# robot_driver_board.net
KiCad netlist of a schematic drawn in EAGLE
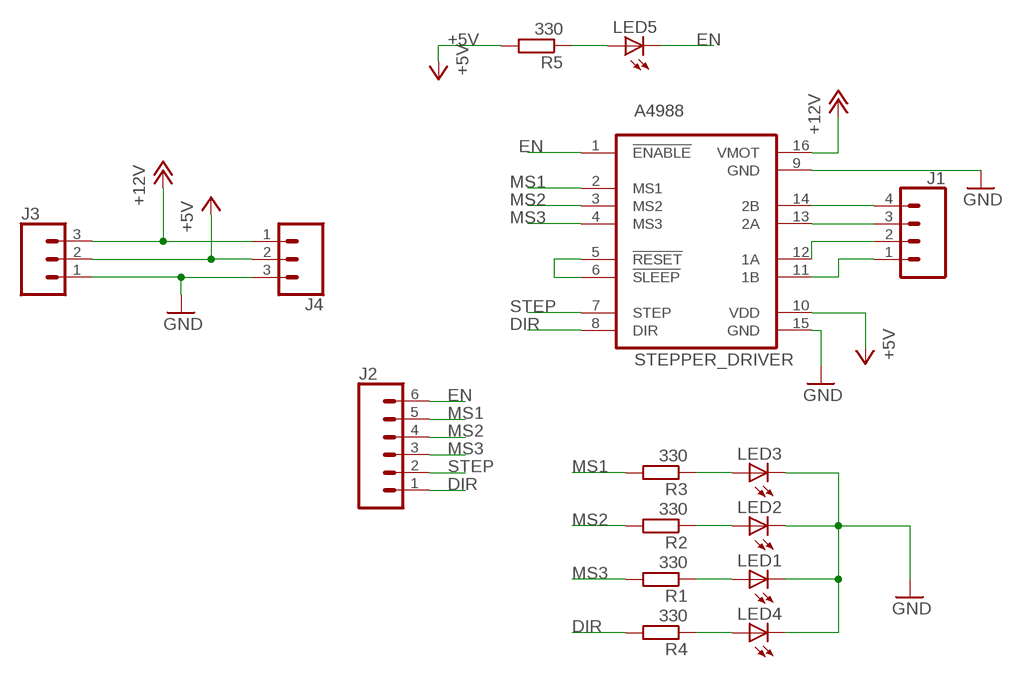
[diagram p0: schematic, sheet 1]

(export (version "E")
  (design (tool "Eeschema 10.0.6"))
  (components
    (comp (ref "J1")
      (value "CONN_04POLAR")
      (footprint "eagle-import:MOLEX-1X4")
      (libsource (lib "eagle-import") (part "CONN_04POLAR"))
    )
    (comp (ref "J2")
      (value "CONN_06POLAR")
      (footprint "eagle-import:MOLEX-1X6")
      (libsource (lib "eagle-import") (part "CONN_06POLAR"))
    )
    (comp (ref "J3")
      (value "CONN_03-SCREW-5MM")
      (footprint "eagle-import:SCREWTERMINAL-5MM-3")
      (libsource (lib "eagle-import") (part "CONN_03-SCREW-5MM"))
    )
    (comp (ref "J4")
      (value "CONN_03-SCREW-5MM")
      (footprint "eagle-import:SCREWTERMINAL-5MM-3")
      (libsource (lib "eagle-import") (part "CONN_03-SCREW-5MM"))
    )
    (comp (ref "LED1")
      (value "LED3MM")
      (footprint "eagle-import:LED3MM")
      (libsource (lib "eagle-import") (part "LED3MM"))
    )
    (comp (ref "LED2")
      (value "LED3MM")
      (footprint "eagle-import:LED3MM")
      (libsource (lib "eagle-import") (part "LED3MM"))
    )
    (comp (ref "LED3")
      (value "LED3MM")
      (footprint "eagle-import:LED3MM")
      (libsource (lib "eagle-import") (part "LED3MM"))
    )
    (comp (ref "LED4")
      (value "LED3MM")
      (footprint "eagle-import:LED3MM")
      (libsource (lib "eagle-import") (part "LED3MM"))
    )
    (comp (ref "LED5")
      (value "LED3MM")
      (footprint "eagle-import:LED3MM")
      (libsource (lib "eagle-import") (part "LED3MM"))
    )
    (comp (ref "R1")
      (value "330")
      (footprint "eagle-import:0207_10")
      (libsource (lib "eagle-import") (part "R-EU_0207/10"))
    )
    (comp (ref "R2")
      (value "330")
      (footprint "eagle-import:0204_7")
      (libsource (lib "eagle-import") (part "R-EU_0204/7"))
    )
    (comp (ref "R3")
      (value "330")
      (footprint "eagle-import:0204_7")
      (libsource (lib "eagle-import") (part "R-EU_0204/7"))
    )
    (comp (ref "R4")
      (value "330")
      (footprint "eagle-import:0204_7")
      (libsource (lib "eagle-import") (part "R-EU_0204/7"))
    )
    (comp (ref "R5")
      (value "330")
      (footprint "eagle-import:0204_7")
      (libsource (lib "eagle-import") (part "R-EU_0204/7"))
    )
    (comp (ref "STEPPER_DRIVER")
      (value "A4988")
      (footprint "eagle-import:POLOLULU2128")
      (libsource (lib "eagle-import") (part "POLOLULU2128"))
    )
  )
  (nets
    (net (code "1") (name "+5V") (class "Default")
      (node (ref "J3") (pin "2") (pinfunction "2_2") (pintype "passive"))
      (node (ref "J4") (pin "2") (pinfunction "2_2") (pintype "passive"))
      (node (ref "R5") (pin "2") (pinfunction "2_2") (pintype "passive"))
      (node (ref "STEPPER_DRIVER") (pin "10") (pinfunction "VDD_10") (pintype "power_in"))
    )
    (net (code "2") (name "+12V") (class "Default")
      (node (ref "J3") (pin "3") (pinfunction "3_3") (pintype "passive"))
      (node (ref "J4") (pin "1") (pinfunction "1_1") (pintype "passive"))
      (node (ref "STEPPER_DRIVER") (pin "16") (pinfunction "VMOT_16") (pintype "power_in"))
    )
    (net (code "3") (name "/DIR") (class "Default")
      (node (ref "J2") (pin "1") (pinfunction "1_1") (pintype "passive"))
      (node (ref "R4") (pin "2") (pinfunction "2_2") (pintype "passive"))
      (node (ref "STEPPER_DRIVER") (pin "8") (pinfunction "DIR_8") (pintype "input"))
    )
    (net (code "4") (name "/EN") (class "Default")
      (node (ref "J2") (pin "6") (pinfunction "6_6") (pintype "passive"))
      (node (ref "LED5") (pin "K") (pinfunction "C_K") (pintype "passive"))
      (node (ref "STEPPER_DRIVER") (pin "1") (pinfunction "~{ENABLE}_1") (pintype "input"))
    )
    (net (code "5") (name "/MS1") (class "Default")
      (node (ref "J2") (pin "5") (pinfunction "5_5") (pintype "passive"))
      (node (ref "R3") (pin "2") (pinfunction "2_2") (pintype "passive"))
      (node (ref "STEPPER_DRIVER") (pin "2") (pinfunction "MS1_2") (pintype "input"))
    )
    (net (code "6") (name "/MS2") (class "Default")
      (node (ref "J2") (pin "4") (pinfunction "4_4") (pintype "passive"))
      (node (ref "R2") (pin "2") (pinfunction "2_2") (pintype "passive"))
      (node (ref "STEPPER_DRIVER") (pin "3") (pinfunction "MS2_3") (pintype "input"))
    )
    (net (code "7") (name "/MS3") (class "Default")
      (node (ref "J2") (pin "3") (pinfunction "3_3") (pintype "passive"))
      (node (ref "R1") (pin "2") (pinfunction "2_2") (pintype "passive"))
      (node (ref "STEPPER_DRIVER") (pin "4") (pinfunction "MS3_4") (pintype "input"))
    )
    (net (code "8") (name "/STEP") (class "Default")
      (node (ref "J2") (pin "2") (pinfunction "2_2") (pintype "passive"))
      (node (ref "STEPPER_DRIVER") (pin "7") (pinfunction "STEP_7") (pintype "input"))
    )
    (net (code "9") (name "GND") (class "Default")
      (node (ref "J3") (pin "1") (pinfunction "1_1") (pintype "passive"))
      (node (ref "J4") (pin "3") (pinfunction "3_3") (pintype "passive"))
      (node (ref "LED1") (pin "K") (pinfunction "C_K") (pintype "passive"))
      (node (ref "LED2") (pin "K") (pinfunction "C_K") (pintype "passive"))
      (node (ref "LED3") (pin "K") (pinfunction "C_K") (pintype "passive"))
      (node (ref "LED4") (pin "K") (pinfunction "C_K") (pintype "passive"))
      (node (ref "STEPPER_DRIVER") (pin "15") (pinfunction "GND_15") (pintype "power_in"))
      (node (ref "STEPPER_DRIVER") (pin "9") (pinfunction "GND_9") (pintype "power_in"))
    )
    (net (code "10") (name "Net-(LED1-PadA)") (class "Default")
      (node (ref "LED1") (pin "A") (pinfunction "A_A") (pintype "passive"))
      (node (ref "R1") (pin "1") (pinfunction "1_1") (pintype "passive"))
    )
    (net (code "11") (name "Net-(LED2-PadA)") (class "Default")
      (node (ref "LED2") (pin "A") (pinfunction "A_A") (pintype "passive"))
      (node (ref "R2") (pin "1") (pinfunction "1_1") (pintype "passive"))
    )
    (net (code "12") (name "Net-(LED3-PadA)") (class "Default")
      (node (ref "LED3") (pin "A") (pinfunction "A_A") (pintype "passive"))
      (node (ref "R3") (pin "1") (pinfunction "1_1") (pintype "passive"))
    )
    (net (code "13") (name "Net-(LED4-PadA)") (class "Default")
      (node (ref "LED4") (pin "A") (pinfunction "A_A") (pintype "passive"))
      (node (ref "R4") (pin "1") (pinfunction "1_1") (pintype "passive"))
    )
    (net (code "14") (name "Net-(LED5-PadA)") (class "Default")
      (node (ref "LED5") (pin "A") (pinfunction "A_A") (pintype "passive"))
      (node (ref "R5") (pin "1") (pinfunction "1_1") (pintype "passive"))
    )
    (net (code "15") (name "Net-(STEPPER_DRIVER-1A)") (class "Default")
      (node (ref "J1") (pin "2") (pinfunction "2_2") (pintype "passive"))
      (node (ref "STEPPER_DRIVER") (pin "12") (pinfunction "1A_12") (pintype "output"))
    )
    (net (code "16") (name "Net-(STEPPER_DRIVER-1B)") (class "Default")
      (node (ref "J1") (pin "1") (pinfunction "1_1") (pintype "passive"))
      (node (ref "STEPPER_DRIVER") (pin "11") (pinfunction "1B_11") (pintype "output"))
    )
    (net (code "17") (name "Net-(STEPPER_DRIVER-2A)") (class "Default")
      (node (ref "J1") (pin "3") (pinfunction "3_3") (pintype "passive"))
      (node (ref "STEPPER_DRIVER") (pin "13") (pinfunction "2A_13") (pintype "output"))
    )
    (net (code "18") (name "Net-(STEPPER_DRIVER-2B)") (class "Default")
      (node (ref "J1") (pin "4") (pinfunction "4_4") (pintype "passive"))
      (node (ref "STEPPER_DRIVER") (pin "14") (pinfunction "2B_14") (pintype "output"))
    )
    (net (code "19") (name "Net-(STEPPER_DRIVER-~{RESET})") (class "Default")
      (node (ref "STEPPER_DRIVER") (pin "5") (pinfunction "~{RESET}_5") (pintype "input"))
      (node (ref "STEPPER_DRIVER") (pin "6") (pinfunction "~{SLEEP}_6") (pintype "input"))
    )
  )
)
